# SCH_WINGLET_WIFI.net
KiCad netlist of a schematic drawn in Altium Designer
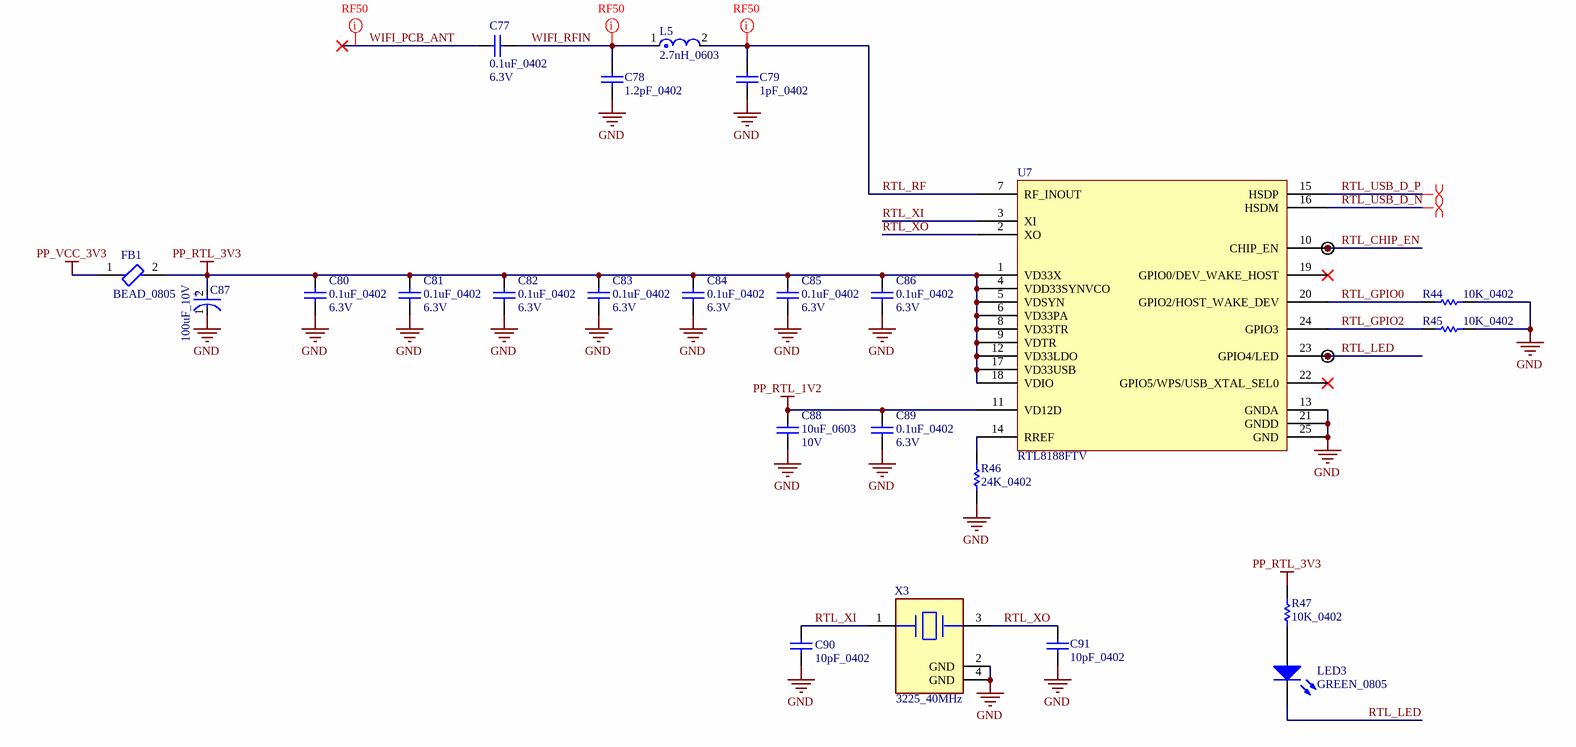
[diagram p0: SCH_WINGLET_WIFI.SchDoc]

(export (version "E")
  (design (tool "Eeschema 10.0.6"))
  (components
    (comp (ref "C77")
      (value "0.1uF_0402")
      (footprint "CAPC1005X56X25NL10T15")
      (description "04026D104KAT2A")
      (fields (field (name "MANUFACTURER") "AVX Interconnect / Elco") (field (name "VOLTAGE RATING") "6.3V"))
      (libsource (lib "Altium Content Vault") (part "CAP"))
    )
    (comp (ref "C78")
      (value "1.2pF_0402")
      (footprint "CAPC1005X61X26NL10T16")
      (description "VJ0402D1R0BXCAJ")
      (fields (field (name "MANUFACTURER") "Vitramon"))
      (libsource (lib "Altium Content Vault") (part "CAP"))
    )
    (comp (ref "C79")
      (value "1pF_0402")
      (footprint "CAPC1005X56X25NL10T15")
      (description "04025A1R2BAT2A")
      (fields (field (name "MANUFACTURER") "AVX Interconnect / Elco"))
      (libsource (lib "Altium Content Vault") (part "CAP"))
    )
    (comp (ref "C80")
      (value "0.1uF_0402")
      (footprint "CAPC1005X56X25NL10T15")
      (description "04026D104KAT2A")
      (fields (field (name "MANUFACTURER") "AVX Interconnect / Elco") (field (name "VOLTAGE RATING") "6.3V"))
      (libsource (lib "Altium Content Vault") (part "CAP"))
    )
    (comp (ref "C81")
      (value "0.1uF_0402")
      (footprint "CAPC1005X56X25NL10T15")
      (description "04026D104KAT2A")
      (fields (field (name "MANUFACTURER") "AVX Interconnect / Elco") (field (name "VOLTAGE RATING") "6.3V"))
      (libsource (lib "Altium Content Vault") (part "CAP"))
    )
    (comp (ref "C82")
      (value "0.1uF_0402")
      (footprint "CAPC1005X56X25NL10T15")
      (description "04026D104KAT2A")
      (fields (field (name "MANUFACTURER") "AVX Interconnect / Elco") (field (name "VOLTAGE RATING") "6.3V"))
      (libsource (lib "Altium Content Vault") (part "CAP"))
    )
    (comp (ref "C83")
      (value "0.1uF_0402")
      (footprint "CAPC1005X56X25NL10T15")
      (description "04026D104KAT2A")
      (fields (field (name "MANUFACTURER") "AVX Interconnect / Elco") (field (name "VOLTAGE RATING") "6.3V"))
      (libsource (lib "Altium Content Vault") (part "CAP"))
    )
    (comp (ref "C84")
      (value "0.1uF_0402")
      (footprint "CAPC1005X56X25NL10T15")
      (description "04026D104KAT2A")
      (fields (field (name "MANUFACTURER") "AVX Interconnect / Elco") (field (name "VOLTAGE RATING") "6.3V"))
      (libsource (lib "Altium Content Vault") (part "CAP"))
    )
    (comp (ref "C85")
      (value "0.1uF_0402")
      (footprint "CAPC1005X56X25NL10T15")
      (description "04026D104KAT2A")
      (fields (field (name "MANUFACTURER") "AVX Interconnect / Elco") (field (name "VOLTAGE RATING") "6.3V"))
      (libsource (lib "Altium Content Vault") (part "CAP"))
    )
    (comp (ref "C86")
      (value "0.1uF_0402")
      (footprint "CAPC1005X56X25NL10T15")
      (description "04026D104KAT2A")
      (fields (field (name "MANUFACTURER") "AVX Interconnect / Elco") (field (name "VOLTAGE RATING") "6.3V"))
      (libsource (lib "Altium Content Vault") (part "CAP"))
    )
    (comp (ref "C87")
      (value "100uF_10V")
      (footprint "FP-TAJB-MFG")
      (description "100uF 10V ±10% 1.7Ω SMD CASE-B (3528) Tantalum Capacitor")
      (fields (field (name "VOLTAGE") "6.3V") (field (name "TOLERANCE") "10%"))
      (libsource (lib "Altium Content Vault") (part "203bc49f2ac43e59fd269a8c329ed05"))
    )
    (comp (ref "C88")
      (value "10uF_0603")
      (footprint "CAPC1609X100X15NL20")
      (fields
        (field (name "PART NUMBER") "TACL106M006XTA")
        (field (name "MANUFACTURER") "AVX Interconnect / Elco")
        (field (name "VOLTAGE RATING") "10V")
      )
      (libsource (lib "Altium Content Vault") (part "CAP"))
    )
    (comp (ref "C89")
      (value "0.1uF_0402")
      (footprint "CAPC1005X56X25NL10T15")
      (description "04026D104KAT2A")
      (fields (field (name "MANUFACTURER") "AVX Interconnect / Elco") (field (name "VOLTAGE RATING") "6.3V"))
      (libsource (lib "Altium Content Vault") (part "CAP"))
    )
    (comp (ref "C90")
      (value "10pF_0402")
      (footprint "CAPC1006X50X20NL10T10")
      (description "0402YJ100FBSTR")
      (fields (field (name "MANUFACTURER") "AVX Interconnect / Elco"))
      (libsource (lib "Altium Content Vault") (part "CAP"))
    )
    (comp (ref "C91")
      (value "10pF_0402")
      (footprint "CAPC1006X50X20NL10T10")
      (description "0402YJ100FBSTR")
      (fields (field (name "MANUFACTURER") "AVX Interconnect / Elco"))
      (libsource (lib "Altium Content Vault") (part "CAP"))
    )
    (comp (ref "FB1")
      (value "BEAD_0805")
      (footprint "FP-BLM21-0_2-t0_85-e0_5-IPC_B")
      (description "Chip Ferrite Bead, 0805, 150Ω @ 100MHz, 0.09Ω, 25%, 1A")
      (fields (field (name "TOLERANCE") "25%"))
      (libsource (lib "Altium Content Vault") (part "5f30dd21d616792df468990f7003faa"))
    )
    (comp (ref "L5")
      (value "2.7nH_0603")
      (footprint "FP-LQG18HH_00-IPC_B")
      (description "Multilayer type RF Inductor 2.7nH ±0.3nH 0.12Ω 1000mA 0603\r\nLQG18HN2N7S00D")
      (libsource (lib "Altium Content Vault") (part "4cc4b267dca4c8e51f7102f422741d8"))
    )
    (comp (ref "LED3")
      (value "GREEN_0805")
      (footprint "0805_A")
      (description "SMD mono-color Chip LED, WL-SMCW, Green\r\n150080GS75000")
      (fields (field (name "PARTNUMBER") "150080GS75000") (field (name "MANUFACTURER") "Wuerth Elektronik"))
      (libsource (lib "Altium Content Vault") (part "WE-LED_K1A2-2"))
    )
    (comp (ref "R44")
      (value "10K_0402")
      (footprint "RESC1005X40X25NL05T05")
      (fields (field (name "TOLERANCE") "1%") (field (name "MANUFACTURER") "Panasonic"))
      (libsource (lib "Altium Content Vault") (part "RES-2"))
    )
    (comp (ref "R45")
      (value "10K_0402")
      (footprint "RESC1005X40X25NL05T05")
      (fields (field (name "TOLERANCE") "1%") (field (name "MANUFACTURER") "Panasonic"))
      (libsource (lib "Altium Content Vault") (part "RES-2"))
    )
    (comp (ref "R46")
      (value "24K_0402")
      (footprint "RESC1005X40X25NL05T05")
      (fields (field (name "TOLERANCE") "1%") (field (name "MANUFACTURER") "Panasonic"))
      (libsource (lib "Altium Content Vault") (part "RES-2"))
    )
    (comp (ref "R47")
      (value "10K_0402")
      (footprint "RESC1005X40X25NL05T05")
      (fields (field (name "TOLERANCE") "1%") (field (name "MANUFACTURER") "Panasonic"))
      (libsource (lib "Altium Content Vault") (part "RES-2"))
    )
    (comp (ref "TP25")
      (value "TESTPOINT")
      (footprint "TESTPOINT-0.7MM-SINGLE-LAYER")
      (description "TESTPOINT SINGLE LAYER 0.7MM")
      (libsource (lib "DCAV32_WINGLET_SCHLIB") (part "TP_07"))
    )
    (comp (ref "TP26")
      (value "TESTPOINT")
      (footprint "TESTPOINT-0.7MM-SINGLE-LAYER")
      (description "TESTPOINT SINGLE LAYER 0.7MM")
      (libsource (lib "DCAV32_WINGLET_SCHLIB") (part "TP_07"))
    )
    (comp (ref "U7")
      (value "RTL8188FTV")
      (footprint "QFN50P400X400X90_HS-25N_RTL")
      (description "Single-chip IEEE 812.11b/g/n 1T1R WLAN")
      (libsource (lib "DCAV32_WINGLET_SCHLIB") (part "RTL8188FTV"))
    )
    (comp (ref "X3")
      (value "3225_40MHz")
      (footprint "FP-ABM8-MFG")
      (description "Crystal 40MHz ±10ppm 10pF SMD-4 3.2mm x 2.5mm\r\nABM8-40.000MHZ-10-1-U-T")
      (fields (field (name "TOLERANCE") "10ppm"))
      (libsource (lib "Altium Content Vault") (part "dfdb7f9a12507849fb681da9a70121c"))
    )
  )
  (nets
    (net (code "1") (name "/RTL_CHIP_EN") (class "Default")
      (node (ref "TP25") (pin "1") (pinfunction "1_1") (pintype "passive"))
      (node (ref "U7") (pin "10") (pinfunction "CHIP_EN_10") (pintype "passive"))
    )
    (net (code "2") (name "/RTL_GPIO0") (class "Default")
      (node (ref "R44") (pin "2") (pinfunction "2_2") (pintype "passive"))
      (node (ref "U7") (pin "20") (pinfunction "GPIO2/HOST_WAKE_DEV_20") (pintype "passive"))
    )
    (net (code "3") (name "/RTL_GPIO2") (class "Default")
      (node (ref "R45") (pin "2") (pinfunction "2_2") (pintype "passive"))
      (node (ref "U7") (pin "24") (pinfunction "GPIO3_24") (pintype "passive"))
    )
    (net (code "4") (name "/RTL_LED") (class "Default")
      (node (ref "LED3") (pin "1") (pinfunction "K_1") (pintype "passive"))
      (node (ref "TP26") (pin "1") (pinfunction "1_1") (pintype "passive"))
      (node (ref "U7") (pin "23") (pinfunction "GPIO4/LED_23") (pintype "passive"))
    )
    (net (code "5") (name "/RTL_RF") (class "Default")
      (node (ref "C79") (pin "2") (pinfunction "2_2") (pintype "passive"))
      (node (ref "L5") (pin "2") (pinfunction "2_2") (pintype "passive"))
      (node (ref "U7") (pin "7") (pinfunction "RF_INOUT_7") (pintype "passive"))
    )
    (net (code "6") (name "/RTL_USB_D_N") (class "Default")
      (node (ref "U7") (pin "16") (pinfunction "HSDM_16") (pintype "passive"))
    )
    (net (code "7") (name "/RTL_USB_D_P") (class "Default")
      (node (ref "U7") (pin "15") (pinfunction "HSDP_15") (pintype "passive"))
    )
    (net (code "8") (name "/RTL_XI") (class "Default")
      (node (ref "C90") (pin "2") (pinfunction "2_2") (pintype "passive"))
      (node (ref "U7") (pin "3") (pinfunction "XI_3") (pintype "passive"))
      (node (ref "X3") (pin "1") (pinfunction "1_1") (pintype "passive"))
    )
    (net (code "9") (name "/RTL_XO") (class "Default")
      (node (ref "C91") (pin "2") (pinfunction "2_2") (pintype "passive"))
      (node (ref "U7") (pin "2") (pinfunction "XO_2") (pintype "passive"))
      (node (ref "X3") (pin "3") (pinfunction "3_3") (pintype "passive"))
    )
    (net (code "10") (name "/WIFI_PCB_ANT") (class "Default")
      (node (ref "C77") (pin "2") (pinfunction "2_2") (pintype "passive+no_connect"))
    )
    (net (code "11") (name "/WIFI_RFIN") (class "Default")
      (node (ref "C77") (pin "1") (pinfunction "1_1") (pintype "passive"))
      (node (ref "C78") (pin "2") (pinfunction "2_2") (pintype "passive"))
      (node (ref "L5") (pin "1") (pinfunction "1_1") (pintype "passive"))
    )
    (net (code "12") (name "GND") (class "Default")
      (node (ref "C78") (pin "1") (pinfunction "1_1") (pintype "passive"))
      (node (ref "C79") (pin "1") (pinfunction "1_1") (pintype "passive"))
      (node (ref "C80") (pin "1") (pinfunction "1_1") (pintype "passive"))
      (node (ref "C81") (pin "1") (pinfunction "1_1") (pintype "passive"))
      (node (ref "C82") (pin "1") (pinfunction "1_1") (pintype "passive"))
      (node (ref "C83") (pin "1") (pinfunction "1_1") (pintype "passive"))
      (node (ref "C84") (pin "1") (pinfunction "1_1") (pintype "passive"))
      (node (ref "C85") (pin "1") (pinfunction "1_1") (pintype "passive"))
      (node (ref "C86") (pin "1") (pinfunction "1_1") (pintype "passive"))
      (node (ref "C87") (pin "1") (pinfunction "C_1") (pintype "passive"))
      (node (ref "C88") (pin "1") (pinfunction "1_1") (pintype "passive"))
      (node (ref "C89") (pin "1") (pinfunction "1_1") (pintype "passive"))
      (node (ref "C90") (pin "1") (pinfunction "1_1") (pintype "passive"))
      (node (ref "C91") (pin "1") (pinfunction "1_1") (pintype "passive"))
      (node (ref "R44") (pin "1") (pinfunction "1_1") (pintype "passive"))
      (node (ref "R45") (pin "1") (pinfunction "1_1") (pintype "passive"))
      (node (ref "R46") (pin "1") (pinfunction "1_1") (pintype "passive"))
      (node (ref "U7") (pin "13") (pinfunction "GNDA_13") (pintype "passive"))
      (node (ref "U7") (pin "21") (pinfunction "GNDD_21") (pintype "passive"))
      (node (ref "U7") (pin "25") (pinfunction "GND_25") (pintype "passive"))
      (node (ref "X3") (pin "2") (pinfunction "GND_2") (pintype "power_in"))
      (node (ref "X3") (pin "4") (pinfunction "GND_4") (pintype "power_in"))
    )
    (net (code "13") (name "Net-(LED3-A)") (class "Default")
      (node (ref "LED3") (pin "2") (pinfunction "A_2") (pintype "passive"))
      (node (ref "R47") (pin "2") (pinfunction "2_2") (pintype "passive"))
    )
    (net (code "14") (name "Net-(U7-RREF)") (class "Default")
      (node (ref "R46") (pin "2") (pinfunction "2_2") (pintype "passive"))
      (node (ref "U7") (pin "14") (pinfunction "RREF_14") (pintype "passive"))
    )
    (net (code "15") (name "PP_RTL_1V2") (class "Default")
      (node (ref "C88") (pin "2") (pinfunction "2_2") (pintype "passive"))
      (node (ref "C89") (pin "2") (pinfunction "2_2") (pintype "passive"))
      (node (ref "U7") (pin "11") (pinfunction "VD12D_11") (pintype "passive"))
    )
    (net (code "16") (name "PP_RTL_3V3") (class "Default")
      (node (ref "C80") (pin "2") (pinfunction "2_2") (pintype "passive"))
      (node (ref "C81") (pin "2") (pinfunction "2_2") (pintype "passive"))
      (node (ref "C82") (pin "2") (pinfunction "2_2") (pintype "passive"))
      (node (ref "C83") (pin "2") (pinfunction "2_2") (pintype "passive"))
      (node (ref "C84") (pin "2") (pinfunction "2_2") (pintype "passive"))
      (node (ref "C85") (pin "2") (pinfunction "2_2") (pintype "passive"))
      (node (ref "C86") (pin "2") (pinfunction "2_2") (pintype "passive"))
      (node (ref "C87") (pin "2") (pinfunction "A_2") (pintype "passive"))
      (node (ref "FB1") (pin "2") (pinfunction "2_2") (pintype "passive"))
      (node (ref "R47") (pin "1") (pinfunction "1_1") (pintype "passive"))
      (node (ref "U7") (pin "1") (pinfunction "VD33X_1") (pintype "passive"))
      (node (ref "U7") (pin "12") (pinfunction "VD33LDO_12") (pintype "passive"))
      (node (ref "U7") (pin "17") (pinfunction "VD33USB_17") (pintype "passive"))
      (node (ref "U7") (pin "18") (pinfunction "VDIO_18") (pintype "passive"))
      (node (ref "U7") (pin "4") (pinfunction "VDD33SYNVCO_4") (pintype "passive"))
      (node (ref "U7") (pin "5") (pinfunction "VDSYN_5") (pintype "passive"))
      (node (ref "U7") (pin "6") (pinfunction "VD33PA_6") (pintype "passive"))
      (node (ref "U7") (pin "8") (pinfunction "VD33TR_8") (pintype "passive"))
      (node (ref "U7") (pin "9") (pinfunction "VDTR_9") (pintype "passive"))
    )
    (net (code "17") (name "PP_VCC_3V3") (class "Default")
      (node (ref "FB1") (pin "1") (pinfunction "1_1") (pintype "passive"))
    )
    (net (code "18") (name "unconnected-(U7-GPIO0{slash}DEV_WAKE_HOST-Pad19)") (class "Default")
      (node (ref "U7") (pin "19") (pinfunction "GPIO0/DEV_WAKE_HOST_19") (pintype "passive+no_connect"))
    )
    (net (code "19") (name "unconnected-(U7-GPIO5{slash}WPS{slash}USB_XTAL_SEL0-Pad22)") (class "Default")
      (node (ref "U7") (pin "22") (pinfunction "GPIO5/WPS/USB_XTAL_SEL0_22") (pintype "passive+no_connect"))
    )
  )
)
